# 03_24V-5V.net
KiCad netlist of a schematic drawn in Altium Designer
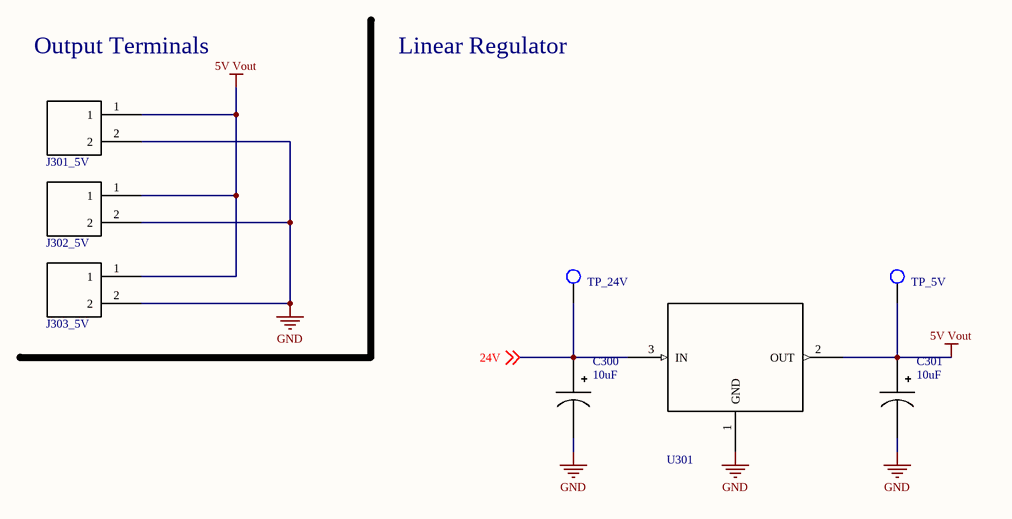
[diagram p0: 03 24V-5V.SchDoc]

(export (version "E")
  (design (tool "Eeschema 10.0.6"))
  (components
    (comp (ref "C300")
      (value "CAP_10uF_TANT")
      (footprint "CAP_1207_POL")
      (fields
        (field (name "MANUFACTURER") "AVX Corporation")
        (field (name "MANUFACTURER PART NUMBER") "F951E106MAAAQ2")
        (field (name "TOLERANCE") "±20%")
        (field (name "CAPACITANCE") "10uF")
      )
      (libsource (lib "ECE453_PWR") (part "CAP_10uF_TANT"))
    )
    (comp (ref "C301")
      (value "CAP_10uF_TANT")
      (footprint "CAP_1207_POL")
      (fields
        (field (name "MANUFACTURER") "AVX Corporation")
        (field (name "MANUFACTURER PART NUMBER") "F951E106MAAAQ2")
        (field (name "TOLERANCE") "±20%")
        (field (name "CAPACITANCE") "10uF")
      )
      (libsource (lib "ECE453_PWR") (part "CAP_10uF_TANT"))
    )
    (comp (ref "J301_5V")
      (value "TERMINAL_SCREW_2x1")
      (footprint "TERM_2Pin")
      (description "TERM BLOCK PLUG 2POS STR 5.08MM")
      (fields
        (field (name "MANUFACTURER") "On Shore Technology Inc.")
        (field (name "MANUFACTURER PART NUMBER") "OSTTJ025153")
      )
      (libsource (lib "ECE453_PWR") (part "TERMINAL_SCREW_2x1"))
    )
    (comp (ref "J302_5V")
      (value "TERMINAL_SCREW_2x1")
      (footprint "TERM_2Pin")
      (description "TERM BLOCK PLUG 2POS STR 5.08MM")
      (fields
        (field (name "MANUFACTURER") "On Shore Technology Inc.")
        (field (name "MANUFACTURER PART NUMBER") "OSTTJ025153")
      )
      (libsource (lib "ECE453_PWR") (part "TERMINAL_SCREW_2x1"))
    )
    (comp (ref "J303_5V")
      (value "TERMINAL_SCREW_2x1")
      (footprint "TERM_2Pin")
      (description "TERM BLOCK PLUG 2POS STR 5.08MM")
      (fields
        (field (name "MANUFACTURER") "On Shore Technology Inc.")
        (field (name "MANUFACTURER PART NUMBER") "OSTTJ025153")
      )
      (libsource (lib "ECE453_PWR") (part "TERMINAL_SCREW_2x1"))
    )
    (comp (ref "TP_5V")
      (value "TP_1206")
      (footprint "TP-SMC-1206")
      (description "Test Point SMD 1206")
      (fields
        (field (name "MANUFACTURER") "TE Connectivity (Tyco Electronics)")
        (field (name "MANUFACTURER PART NUMBER") "1625854-1")
      )
      (libsource (lib "ECE453_PWR") (part "TP_1206"))
    )
    (comp (ref "TP_24V")
      (value "TP_1206")
      (footprint "TP-SMC-1206")
      (description "Test Point SMD 1206")
      (fields
        (field (name "MANUFACTURER") "TE Connectivity (Tyco Electronics)")
        (field (name "MANUFACTURER PART NUMBER") "1625854-1")
      )
      (libsource (lib "ECE453_PWR") (part "TP_1206"))
    )
    (comp (ref "U301")
      (value "BUCK_LM1084IS-5.0")
      (footprint "BUCK_5V_OUT_FIXED")
      (fields
        (field (name "MANUFACTURER") "Texas Instruments")
        (field (name "MANUFACTURER PART NUMBER") "LM1084ISX-5.0/NOPB")
        (field (name "BASE PART NUMBER") "LM1084")
      )
      (libsource (lib "ECE453_PWR") (part "BUCK_LM1084IS-5.0"))
    )
  )
  (nets
    (net (code "1") (name "5V Vout") (class "Default")
      (node (ref "C301") (pin "1") (pinfunction "+_1") (pintype "passive"))
      (node (ref "J301_5V") (pin "1") (pinfunction "1_1") (pintype "passive"))
      (node (ref "J302_5V") (pin "1") (pinfunction "1_1") (pintype "passive"))
      (node (ref "J303_5V") (pin "1") (pinfunction "1_1") (pintype "passive"))
      (node (ref "TP_5V") (pin "1") (pintype "passive"))
      (node (ref "U301") (pin "2") (pinfunction "OUT_2") (pintype "output"))
    )
    (net (code "2") (name "24V") (class "Default")
      (node (ref "C300") (pin "1") (pinfunction "+_1") (pintype "passive"))
      (node (ref "TP_24V") (pin "1") (pintype "passive"))
      (node (ref "U301") (pin "3") (pinfunction "IN_3") (pintype "input"))
    )
    (net (code "3") (name "GND") (class "Default")
      (node (ref "C300") (pin "2") (pinfunction "-_2") (pintype "passive"))
      (node (ref "C301") (pin "2") (pinfunction "-_2") (pintype "passive"))
      (node (ref "J301_5V") (pin "2") (pinfunction "2_2") (pintype "passive"))
      (node (ref "J302_5V") (pin "2") (pinfunction "2_2") (pintype "passive"))
      (node (ref "J303_5V") (pin "2") (pinfunction "2_2") (pintype "passive"))
      (node (ref "U301") (pin "1") (pinfunction "GND_1") (pintype "power_in"))
    )
  )
)
